# EM78M611RX.net
KiCad netlist of a schematic drawn in Altium Designer
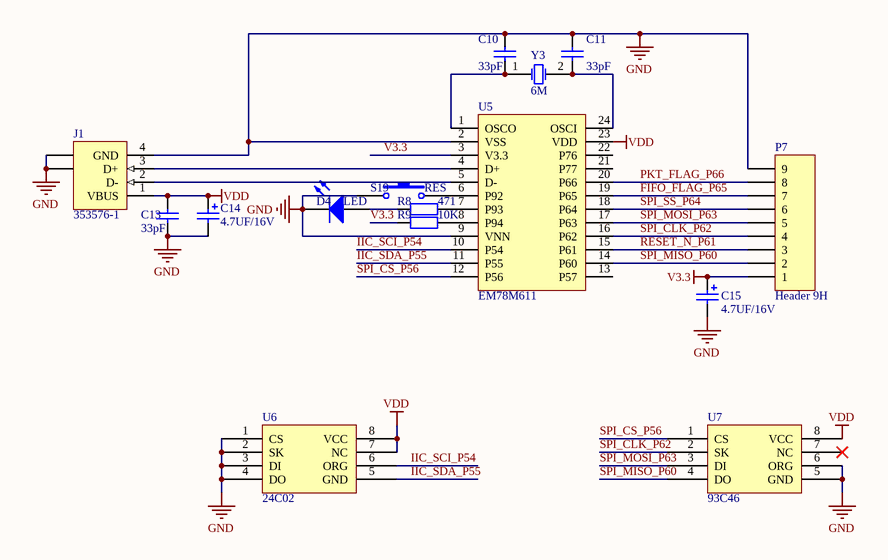
[diagram p0: EM78M611RX.SchDoc]

(export (version "E")
  (design (tool "Eeschema 10.0.6"))
  (components
    (comp (ref "C10")
      (value "33pF")
      (footprint "c0805")
      (description "Capacitor")
      (fields (field (name "Comment") "Cap") (field (name "PUBLISHER") "Altium Limited"))
      (libsource (lib "EM78P510_EM78M611_EM198810") (part "Cap"))
    )
    (comp (ref "C11")
      (value "33pF")
      (footprint "c0805")
      (description "Capacitor")
      (fields (field (name "Comment") "Cap") (field (name "PUBLISHER") "Altium Limited"))
      (libsource (lib "EM78P510_EM78M611_EM198810") (part "Cap"))
    )
    (comp (ref "C13")
      (value "33pF")
      (footprint "c0805")
      (description "Capacitor")
      (fields (field (name "Comment") "Cap") (field (name "PUBLISHER") "Altium Limited"))
      (libsource (lib "EM78P510_EM78M611_EM198810") (part "Cap"))
    )
    (comp (ref "C14")
      (value "4.7UF/16V")
      (footprint "C1206-2")
      (description "Polarized Capacitor (Radial)")
      (fields (field (name "Comment") "Cap Pol1") (field (name "PUBLISHER") "Altium Limited"))
      (libsource (lib "EM78P510_EM78M611_EM198810") (part "Cap Pol1"))
    )
    (comp (ref "C15")
      (value "4.7UF/16V")
      (footprint "RB5")
      (description "Polarized Capacitor (Radial)")
      (fields (field (name "Comment") "Cap Pol1") (field (name "PUBLISHER") "Altium Limited"))
      (libsource (lib "EM78P510_EM78M611_EM198810") (part "Cap Pol1"))
    )
    (comp (ref "D4")
      (value "LED")
      (footprint "led-3")
      (description "Typical INFRARED GaAs LED")
      (fields (field (name "PUBLISHER") "Altium Limited"))
      (libsource (lib "EM78P510_EM78M611_EM198810") (part "LED0"))
    )
    (comp (ref "J1")
      (value "353576-1")
      (footprint "USBSD")
      (description "USB 1.1, Right Angle, SMT, A Type, Receptacle, 4 Position, White")
      (fields (field (name "PUBLISHER") "Altium Limited"))
      (libsource (lib "AMP Serial Bus USB") (part "353576-1"))
    )
    (comp (ref "P7")
      (value "Header 9H")
      (footprint "rfm")
      (description "Header, 9-Pin, Right Angle")
      (fields (field (name "PUBLISHER") "Altium Limited"))
      (libsource (lib "EM78P510_EM78M611_EM198810") (part "Header 9H"))
    )
    (comp (ref "R8")
      (value "471")
      (footprint "R0805")
      (description "Resistor")
      (fields (field (name "Comment") "Res2") (field (name "PUBLISHER") "Altium Limited"))
      (libsource (lib "EM78P510_EM78M611_EM198810") (part "Res2"))
    )
    (comp (ref "R9")
      (value "10K")
      (footprint "R0805")
      (description "Resistor")
      (fields (field (name "Comment") "Res2") (field (name "PUBLISHER") "Altium Limited"))
      (libsource (lib "EM78P510_EM78M611_EM198810") (part "Res2"))
    )
    (comp (ref "S19")
      (value "RES")
      (footprint "SW-PB")
      (description "Switch")
      (fields (field (name "PUBLISHER") "Altium Limited"))
      (libsource (lib "EM78P510_EM78M611_EM198810") (part "SW-PB"))
    )
    (comp (ref "U5")
      (value "EM78M611")
      (footprint "DIP24")
      (libsource (lib "EM78P510_EM78M611_EM198810") (part "EM78M611-24"))
    )
    (comp (ref "U6")
      (value "24C02")
      (footprint "sop8")
      (libsource (lib "EM78P510_EM78M611_EM198810") (part "24C02"))
    )
    (comp (ref "U7")
      (value "93C46")
      (footprint "sop8")
      (libsource (lib "EM78P510_EM78M611_EM198810") (part "93C46"))
    )
    (comp (ref "Y3")
      (value "6M")
      (footprint "CRY")
      (description "Crystal Oscillator")
      (fields (field (name "PUBLISHER") "Altium Limited"))
      (libsource (lib "EM78P510_EM78M611_EM198810") (part "XTAL"))
    )
  )
  (nets
    (net (code "1") (name "/FIFO_FLAG_P65") (class "Default")
      (node (ref "P7") (pin "7") (pinfunction "7_7") (pintype "passive"))
      (node (ref "U5") (pin "19") (pinfunction "P65_19") (pintype "passive"))
    )
    (net (code "2") (name "/IIC_SCI_P54") (class "Default")
      (node (ref "U5") (pin "10") (pinfunction "P54_10") (pintype "passive"))
      (node (ref "U6") (pin "6") (pinfunction "ORG_6") (pintype "passive"))
    )
    (net (code "3") (name "/IIC_SDA_P55") (class "Default")
      (node (ref "U5") (pin "11") (pinfunction "P55_11") (pintype "passive"))
      (node (ref "U6") (pin "5") (pinfunction "GND_5") (pintype "passive"))
    )
    (net (code "4") (name "/PKT_FLAG_P66") (class "Default")
      (node (ref "P7") (pin "8") (pinfunction "8_8") (pintype "passive"))
      (node (ref "U5") (pin "20") (pinfunction "P66_20") (pintype "passive"))
    )
    (net (code "5") (name "/RESET_N_P61") (class "Default")
      (node (ref "P7") (pin "3") (pinfunction "3_3") (pintype "passive"))
      (node (ref "U5") (pin "15") (pinfunction "P61_15") (pintype "passive"))
    )
    (net (code "6") (name "/SPI_CLK_P62") (class "Default")
      (node (ref "P7") (pin "4") (pinfunction "4_4") (pintype "passive"))
      (node (ref "U5") (pin "16") (pinfunction "P62_16") (pintype "passive"))
      (node (ref "U7") (pin "2") (pinfunction "SK_2") (pintype "passive"))
    )
    (net (code "7") (name "/SPI_CS_P56") (class "Default")
      (node (ref "U5") (pin "12") (pinfunction "P56_12") (pintype "passive"))
      (node (ref "U7") (pin "1") (pinfunction "CS_1") (pintype "passive"))
    )
    (net (code "8") (name "/SPI_MISO_P60") (class "Default")
      (node (ref "P7") (pin "2") (pinfunction "2_2") (pintype "passive"))
      (node (ref "U5") (pin "14") (pinfunction "P60_14") (pintype "passive"))
      (node (ref "U7") (pin "4") (pinfunction "DO_4") (pintype "passive"))
    )
    (net (code "9") (name "/SPI_MOSI_P63") (class "Default")
      (node (ref "P7") (pin "5") (pinfunction "5_5") (pintype "passive"))
      (node (ref "U5") (pin "17") (pinfunction "P63_17") (pintype "passive"))
      (node (ref "U7") (pin "3") (pinfunction "DI_3") (pintype "passive"))
    )
    (net (code "10") (name "/SPI_SS_P64") (class "Default")
      (node (ref "P7") (pin "6") (pinfunction "6_6") (pintype "passive"))
      (node (ref "U5") (pin "18") (pinfunction "P64_18") (pintype "passive"))
    )
    (net (code "11") (name "GND") (class "Default")
      (node (ref "C10") (pin "1") (pinfunction "1_1") (pintype "passive"))
      (node (ref "C11") (pin "2") (pinfunction "2_2") (pintype "passive"))
      (node (ref "C13") (pin "1") (pinfunction "1_1") (pintype "passive"))
      (node (ref "C14") (pin "2") (pinfunction "2_2") (pintype "passive"))
      (node (ref "C15") (pin "2") (pinfunction "2_2") (pintype "passive"))
      (node (ref "D4") (pin "2") (pinfunction "K_2") (pintype "passive"))
      (node (ref "J1") (pin "4") (pinfunction "GND_4") (pintype "power_in"))
      (node (ref "J1") (pin "5") (pinfunction "SHLD_5") (pintype "passive"))
      (node (ref "J1") (pin "6") (pinfunction "SHLD_6") (pintype "passive"))
      (node (ref "P7") (pin "9") (pinfunction "9_9") (pintype "passive"))
      (node (ref "S19") (pin "1") (pinfunction "1_1") (pintype "passive"))
      (node (ref "U5") (pin "2") (pinfunction "VSS_2") (pintype "passive"))
      (node (ref "U5") (pin "9") (pinfunction "VNN_9") (pintype "passive"))
      (node (ref "U6") (pin "1") (pinfunction "CS_1") (pintype "passive"))
      (node (ref "U6") (pin "2") (pinfunction "SK_2") (pintype "passive"))
      (node (ref "U6") (pin "3") (pinfunction "DI_3") (pintype "passive"))
      (node (ref "U6") (pin "4") (pinfunction "DO_4") (pintype "passive"))
      (node (ref "U7") (pin "5") (pinfunction "GND_5") (pintype "passive"))
      (node (ref "U7") (pin "6") (pinfunction "ORG_6") (pintype "passive"))
    )
    (net (code "12") (name "Net-(D4-A)") (class "Default")
      (node (ref "D4") (pin "1") (pinfunction "A_1") (pintype "passive"))
      (node (ref "R8") (pin "1") (pinfunction "1_1") (pintype "passive"))
    )
    (net (code "13") (name "Net-(J1-D+)") (class "Default")
      (node (ref "J1") (pin "3") (pinfunction "D+_3") (pintype "input"))
      (node (ref "U5") (pin "4") (pinfunction "D+_4") (pintype "passive"))
    )
    (net (code "14") (name "Net-(J1-D-)") (class "Default")
      (node (ref "J1") (pin "2") (pinfunction "D-_2") (pintype "input"))
      (node (ref "U5") (pin "5") (pinfunction "D-_5") (pintype "passive"))
    )
    (net (code "15") (name "Net-(U5-OSCI)") (class "Default")
      (node (ref "C11") (pin "1") (pinfunction "1_1") (pintype "passive"))
      (node (ref "U5") (pin "24") (pinfunction "OSCI_24") (pintype "passive"))
      (node (ref "Y3") (pin "2") (pinfunction "OSC2_2") (pintype "passive"))
    )
    (net (code "16") (name "Net-(U5-OSCO)") (class "Default")
      (node (ref "C10") (pin "2") (pinfunction "2_2") (pintype "passive"))
      (node (ref "U5") (pin "1") (pinfunction "OSCO_1") (pintype "passive"))
      (node (ref "Y3") (pin "1") (pinfunction "OSC1_1") (pintype "passive"))
    )
    (net (code "17") (name "Net-(U5-P92)") (class "Default")
      (node (ref "S19") (pin "2") (pinfunction "2_2") (pintype "passive"))
      (node (ref "U5") (pin "6") (pinfunction "P92_6") (pintype "passive"))
    )
    (net (code "18") (name "Net-(U5-P93)") (class "Default")
      (node (ref "R8") (pin "2") (pinfunction "2_2") (pintype "passive"))
      (node (ref "U5") (pin "7") (pinfunction "P93_7") (pintype "passive"))
    )
    (net (code "19") (name "Net-(U5-P94)") (class "Default")
      (node (ref "R9") (pin "2") (pinfunction "2_2") (pintype "passive"))
      (node (ref "U5") (pin "8") (pinfunction "P94_8") (pintype "passive"))
    )
    (net (code "20") (name "V3.3") (class "Default")
      (node (ref "C15") (pin "1") (pinfunction "1_1") (pintype "passive"))
      (node (ref "P7") (pin "1") (pinfunction "1_1") (pintype "passive"))
      (node (ref "R9") (pin "1") (pinfunction "1_1") (pintype "passive"))
      (node (ref "U5") (pin "3") (pinfunction "V3.3_3") (pintype "passive"))
    )
    (net (code "21") (name "VDD") (class "Default")
      (node (ref "C13") (pin "2") (pinfunction "2_2") (pintype "passive"))
      (node (ref "C14") (pin "1") (pinfunction "1_1") (pintype "passive"))
      (node (ref "J1") (pin "1") (pinfunction "VBUS_1") (pintype "power_in"))
      (node (ref "U5") (pin "23") (pinfunction "VDD_23") (pintype "passive"))
      (node (ref "U6") (pin "7") (pinfunction "NC_7") (pintype "passive"))
      (node (ref "U6") (pin "8") (pinfunction "VCC_8") (pintype "passive"))
      (node (ref "U7") (pin "8") (pinfunction "VCC_8") (pintype "passive"))
    )
    (net (code "22") (name "unconnected-(U5-P57-Pad13)") (class "Default")
      (node (ref "U5") (pin "13") (pinfunction "P57_13") (pintype "passive"))
    )
    (net (code "23") (name "unconnected-(U5-P76-Pad22)") (class "Default")
      (node (ref "U5") (pin "22") (pinfunction "P76_22") (pintype "passive"))
    )
    (net (code "24") (name "unconnected-(U5-P77-Pad21)") (class "Default")
      (node (ref "U5") (pin "21") (pinfunction "P77_21") (pintype "passive"))
    )
    (net (code "25") (name "unconnected-(U7-NC-Pad7)") (class "Default")
      (node (ref "U7") (pin "7") (pinfunction "NC_7") (pintype "passive+no_connect"))
    )
  )
)
